# pca_full.net
KiCad netlist of a schematic drawn in EAGLE
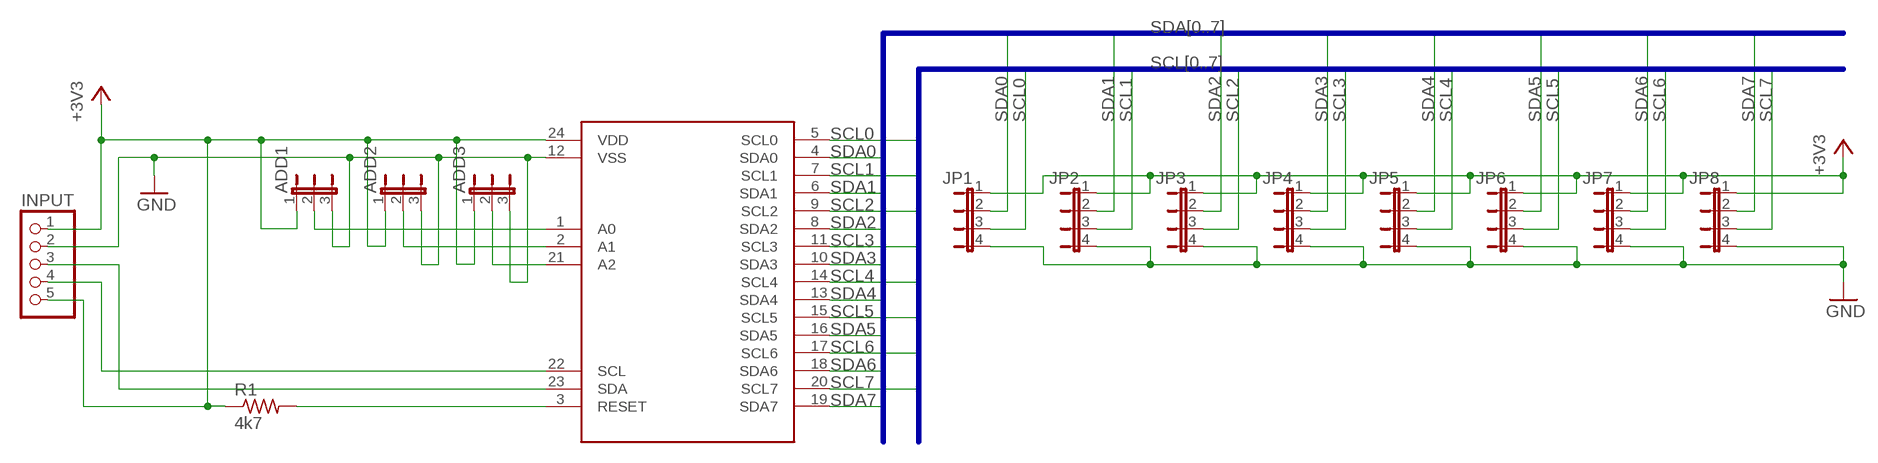
[diagram p0: schematic, sheet 1]

(export (version "E")
  (design (tool "Eeschema 10.0.6"))
  (components
    (comp (ref "ADD1")
      (value "JP2E")
      (footprint "eagle-import:JP2")
      (libsource (lib "eagle-import") (part "JP2E"))
    )
    (comp (ref "ADD2")
      (value "JP2E")
      (footprint "eagle-import:JP2")
      (libsource (lib "eagle-import") (part "JP2E"))
    )
    (comp (ref "ADD3")
      (value "JP2E")
      (footprint "eagle-import:JP2")
      (libsource (lib "eagle-import") (part "JP2E"))
    )
    (comp (ref "INPUT")
      (value "PINHD-1X5")
      (footprint "eagle-import:1X05")
      (libsource (lib "eagle-import") (part "PINHD-1X5"))
    )
    (comp (ref "JP1")
      (value "JP4E")
      (footprint "eagle-import:JP4")
      (libsource (lib "eagle-import") (part "JP4E"))
    )
    (comp (ref "JP2")
      (value "JP4E")
      (footprint "eagle-import:JP4")
      (libsource (lib "eagle-import") (part "JP4E"))
    )
    (comp (ref "JP3")
      (value "JP4E")
      (footprint "eagle-import:JP4")
      (libsource (lib "eagle-import") (part "JP4E"))
    )
    (comp (ref "JP4")
      (value "JP4E")
      (footprint "eagle-import:JP4")
      (libsource (lib "eagle-import") (part "JP4E"))
    )
    (comp (ref "JP5")
      (value "JP4E")
      (footprint "eagle-import:JP4")
      (libsource (lib "eagle-import") (part "JP4E"))
    )
    (comp (ref "JP6")
      (value "JP4E")
      (footprint "eagle-import:JP4")
      (libsource (lib "eagle-import") (part "JP4E"))
    )
    (comp (ref "JP7")
      (value "JP4E")
      (footprint "eagle-import:JP4")
      (libsource (lib "eagle-import") (part "JP4E"))
    )
    (comp (ref "JP8")
      (value "JP4E")
      (footprint "eagle-import:JP4")
      (libsource (lib "eagle-import") (part "JP4E"))
    )
    (comp (ref "R1")
      (value "4k7")
      (footprint "eagle-import:0204_5")
      (libsource (lib "eagle-import") (part "R-US_0204/5"))
    )
    (comp (ref "U$1")
      (value "PCA9547")
      (footprint "eagle-import:SO24")
      (libsource (lib "eagle-import") (part "PCA9547"))
    )
  )
  (nets
    (net (code "1") (name "+3V3") (class "Default")
      (node (ref "ADD1") (pin "1") (pinfunction "1_1") (pintype "passive"))
      (node (ref "ADD2") (pin "1") (pinfunction "1_1") (pintype "passive"))
      (node (ref "ADD3") (pin "1") (pinfunction "1_1") (pintype "passive"))
      (node (ref "INPUT") (pin "1") (pinfunction "1_1") (pintype "passive"))
      (node (ref "INPUT") (pin "5") (pinfunction "5_5") (pintype "passive"))
      (node (ref "JP1") (pin "1") (pinfunction "1_1") (pintype "passive"))
      (node (ref "JP2") (pin "1") (pinfunction "1_1") (pintype "passive"))
      (node (ref "JP3") (pin "1") (pinfunction "1_1") (pintype "passive"))
      (node (ref "JP4") (pin "1") (pinfunction "1_1") (pintype "passive"))
      (node (ref "JP5") (pin "1") (pinfunction "1_1") (pintype "passive"))
      (node (ref "JP6") (pin "1") (pinfunction "1_1") (pintype "passive"))
      (node (ref "JP7") (pin "1") (pinfunction "1_1") (pintype "passive"))
      (node (ref "JP8") (pin "1") (pinfunction "1_1") (pintype "passive"))
      (node (ref "R1") (pin "1") (pinfunction "1_1") (pintype "passive"))
      (node (ref "U$1") (pin "24") (pinfunction "VDD_24") (pintype "power_in"))
    )
    (net (code "2") (name "/SCL0") (class "Default")
      (node (ref "JP1") (pin "3") (pinfunction "3_3") (pintype "passive"))
      (node (ref "U$1") (pin "5") (pinfunction "SCL0_5") (pintype "bidirectional"))
    )
    (net (code "3") (name "/SCL1") (class "Default")
      (node (ref "JP2") (pin "3") (pinfunction "3_3") (pintype "passive"))
      (node (ref "U$1") (pin "7") (pinfunction "SCL1_7") (pintype "bidirectional"))
    )
    (net (code "4") (name "/SCL2") (class "Default")
      (node (ref "JP3") (pin "3") (pinfunction "3_3") (pintype "passive"))
      (node (ref "U$1") (pin "9") (pinfunction "SCL2_9") (pintype "bidirectional"))
    )
    (net (code "5") (name "/SCL3") (class "Default")
      (node (ref "JP4") (pin "3") (pinfunction "3_3") (pintype "passive"))
      (node (ref "U$1") (pin "11") (pinfunction "SCL3_11") (pintype "bidirectional"))
    )
    (net (code "6") (name "/SCL4") (class "Default")
      (node (ref "JP5") (pin "3") (pinfunction "3_3") (pintype "passive"))
      (node (ref "U$1") (pin "14") (pinfunction "SCL4_14") (pintype "bidirectional"))
    )
    (net (code "7") (name "/SCL5") (class "Default")
      (node (ref "JP6") (pin "3") (pinfunction "3_3") (pintype "passive"))
      (node (ref "U$1") (pin "15") (pinfunction "SCL5_15") (pintype "bidirectional"))
    )
    (net (code "8") (name "/SCL6") (class "Default")
      (node (ref "JP7") (pin "3") (pinfunction "3_3") (pintype "passive"))
      (node (ref "U$1") (pin "17") (pinfunction "SCL6_17") (pintype "bidirectional"))
    )
    (net (code "9") (name "/SCL7") (class "Default")
      (node (ref "JP8") (pin "3") (pinfunction "3_3") (pintype "passive"))
      (node (ref "U$1") (pin "20") (pinfunction "SCL7_20") (pintype "bidirectional"))
    )
    (net (code "11") (name "/SDA0") (class "Default")
      (node (ref "JP1") (pin "2") (pinfunction "2_2") (pintype "passive"))
      (node (ref "U$1") (pin "4") (pinfunction "SDA0_4") (pintype "bidirectional"))
    )
    (net (code "12") (name "/SDA1") (class "Default")
      (node (ref "JP2") (pin "2") (pinfunction "2_2") (pintype "passive"))
      (node (ref "U$1") (pin "6") (pinfunction "SDA1_6") (pintype "bidirectional"))
    )
    (net (code "13") (name "/SDA2") (class "Default")
      (node (ref "JP3") (pin "2") (pinfunction "2_2") (pintype "passive"))
      (node (ref "U$1") (pin "8") (pinfunction "SDA2_8") (pintype "bidirectional"))
    )
    (net (code "14") (name "/SDA3") (class "Default")
      (node (ref "JP4") (pin "2") (pinfunction "2_2") (pintype "passive"))
      (node (ref "U$1") (pin "10") (pinfunction "SDA3_10") (pintype "bidirectional"))
    )
    (net (code "15") (name "/SDA4") (class "Default")
      (node (ref "JP5") (pin "2") (pinfunction "2_2") (pintype "passive"))
      (node (ref "U$1") (pin "13") (pinfunction "SDA4_13") (pintype "bidirectional"))
    )
    (net (code "16") (name "/SDA5") (class "Default")
      (node (ref "JP6") (pin "2") (pinfunction "2_2") (pintype "passive"))
      (node (ref "U$1") (pin "16") (pinfunction "SDA5_16") (pintype "bidirectional"))
    )
    (net (code "17") (name "/SDA6") (class "Default")
      (node (ref "JP7") (pin "2") (pinfunction "2_2") (pintype "passive"))
      (node (ref "U$1") (pin "18") (pinfunction "SDA6_18") (pintype "bidirectional"))
    )
    (net (code "18") (name "/SDA7") (class "Default")
      (node (ref "JP8") (pin "2") (pinfunction "2_2") (pintype "passive"))
      (node (ref "U$1") (pin "19") (pinfunction "SDA7_19") (pintype "bidirectional"))
    )
    (net (code "20") (name "GND") (class "Default")
      (node (ref "ADD1") (pin "3") (pinfunction "3_3") (pintype "passive"))
      (node (ref "ADD2") (pin "3") (pinfunction "3_3") (pintype "passive"))
      (node (ref "ADD3") (pin "3") (pinfunction "3_3") (pintype "passive"))
      (node (ref "INPUT") (pin "2") (pinfunction "2_2") (pintype "passive"))
      (node (ref "JP1") (pin "4") (pinfunction "4_4") (pintype "passive"))
      (node (ref "JP2") (pin "4") (pinfunction "4_4") (pintype "passive"))
      (node (ref "JP3") (pin "4") (pinfunction "4_4") (pintype "passive"))
      (node (ref "JP4") (pin "4") (pinfunction "4_4") (pintype "passive"))
      (node (ref "JP5") (pin "4") (pinfunction "4_4") (pintype "passive"))
      (node (ref "JP6") (pin "4") (pinfunction "4_4") (pintype "passive"))
      (node (ref "JP7") (pin "4") (pinfunction "4_4") (pintype "passive"))
      (node (ref "JP8") (pin "4") (pinfunction "4_4") (pintype "passive"))
      (node (ref "U$1") (pin "12") (pinfunction "VSS_12") (pintype "power_in"))
    )
    (net (code "21") (name "Net-(U$1-A0)") (class "Default")
      (node (ref "ADD1") (pin "2") (pinfunction "2_2") (pintype "passive"))
      (node (ref "U$1") (pin "1") (pinfunction "A0_1") (pintype "input"))
    )
    (net (code "22") (name "Net-(U$1-A1)") (class "Default")
      (node (ref "ADD2") (pin "2") (pinfunction "2_2") (pintype "passive"))
      (node (ref "U$1") (pin "2") (pinfunction "A1_2") (pintype "input"))
    )
    (net (code "23") (name "Net-(U$1-A2)") (class "Default")
      (node (ref "ADD3") (pin "2") (pinfunction "2_2") (pintype "passive"))
      (node (ref "U$1") (pin "21") (pinfunction "A2_21") (pintype "input"))
    )
    (net (code "24") (name "Net-(U$1-RESET)") (class "Default")
      (node (ref "R1") (pin "2") (pinfunction "2_2") (pintype "passive"))
      (node (ref "U$1") (pin "3") (pinfunction "RESET_3") (pintype "input"))
    )
    (net (code "25") (name "Net-(U$1-SCL)") (class "Default")
      (node (ref "INPUT") (pin "4") (pinfunction "4_4") (pintype "passive"))
      (node (ref "U$1") (pin "22") (pinfunction "SCL_22") (pintype "bidirectional"))
    )
    (net (code "26") (name "Net-(U$1-SDA)") (class "Default")
      (node (ref "INPUT") (pin "3") (pinfunction "3_3") (pintype "passive"))
      (node (ref "U$1") (pin "23") (pinfunction "SDA_23") (pintype "bidirectional"))
    )
  )
)
